# controller.net
KiCad netlist of a schematic drawn in EAGLE
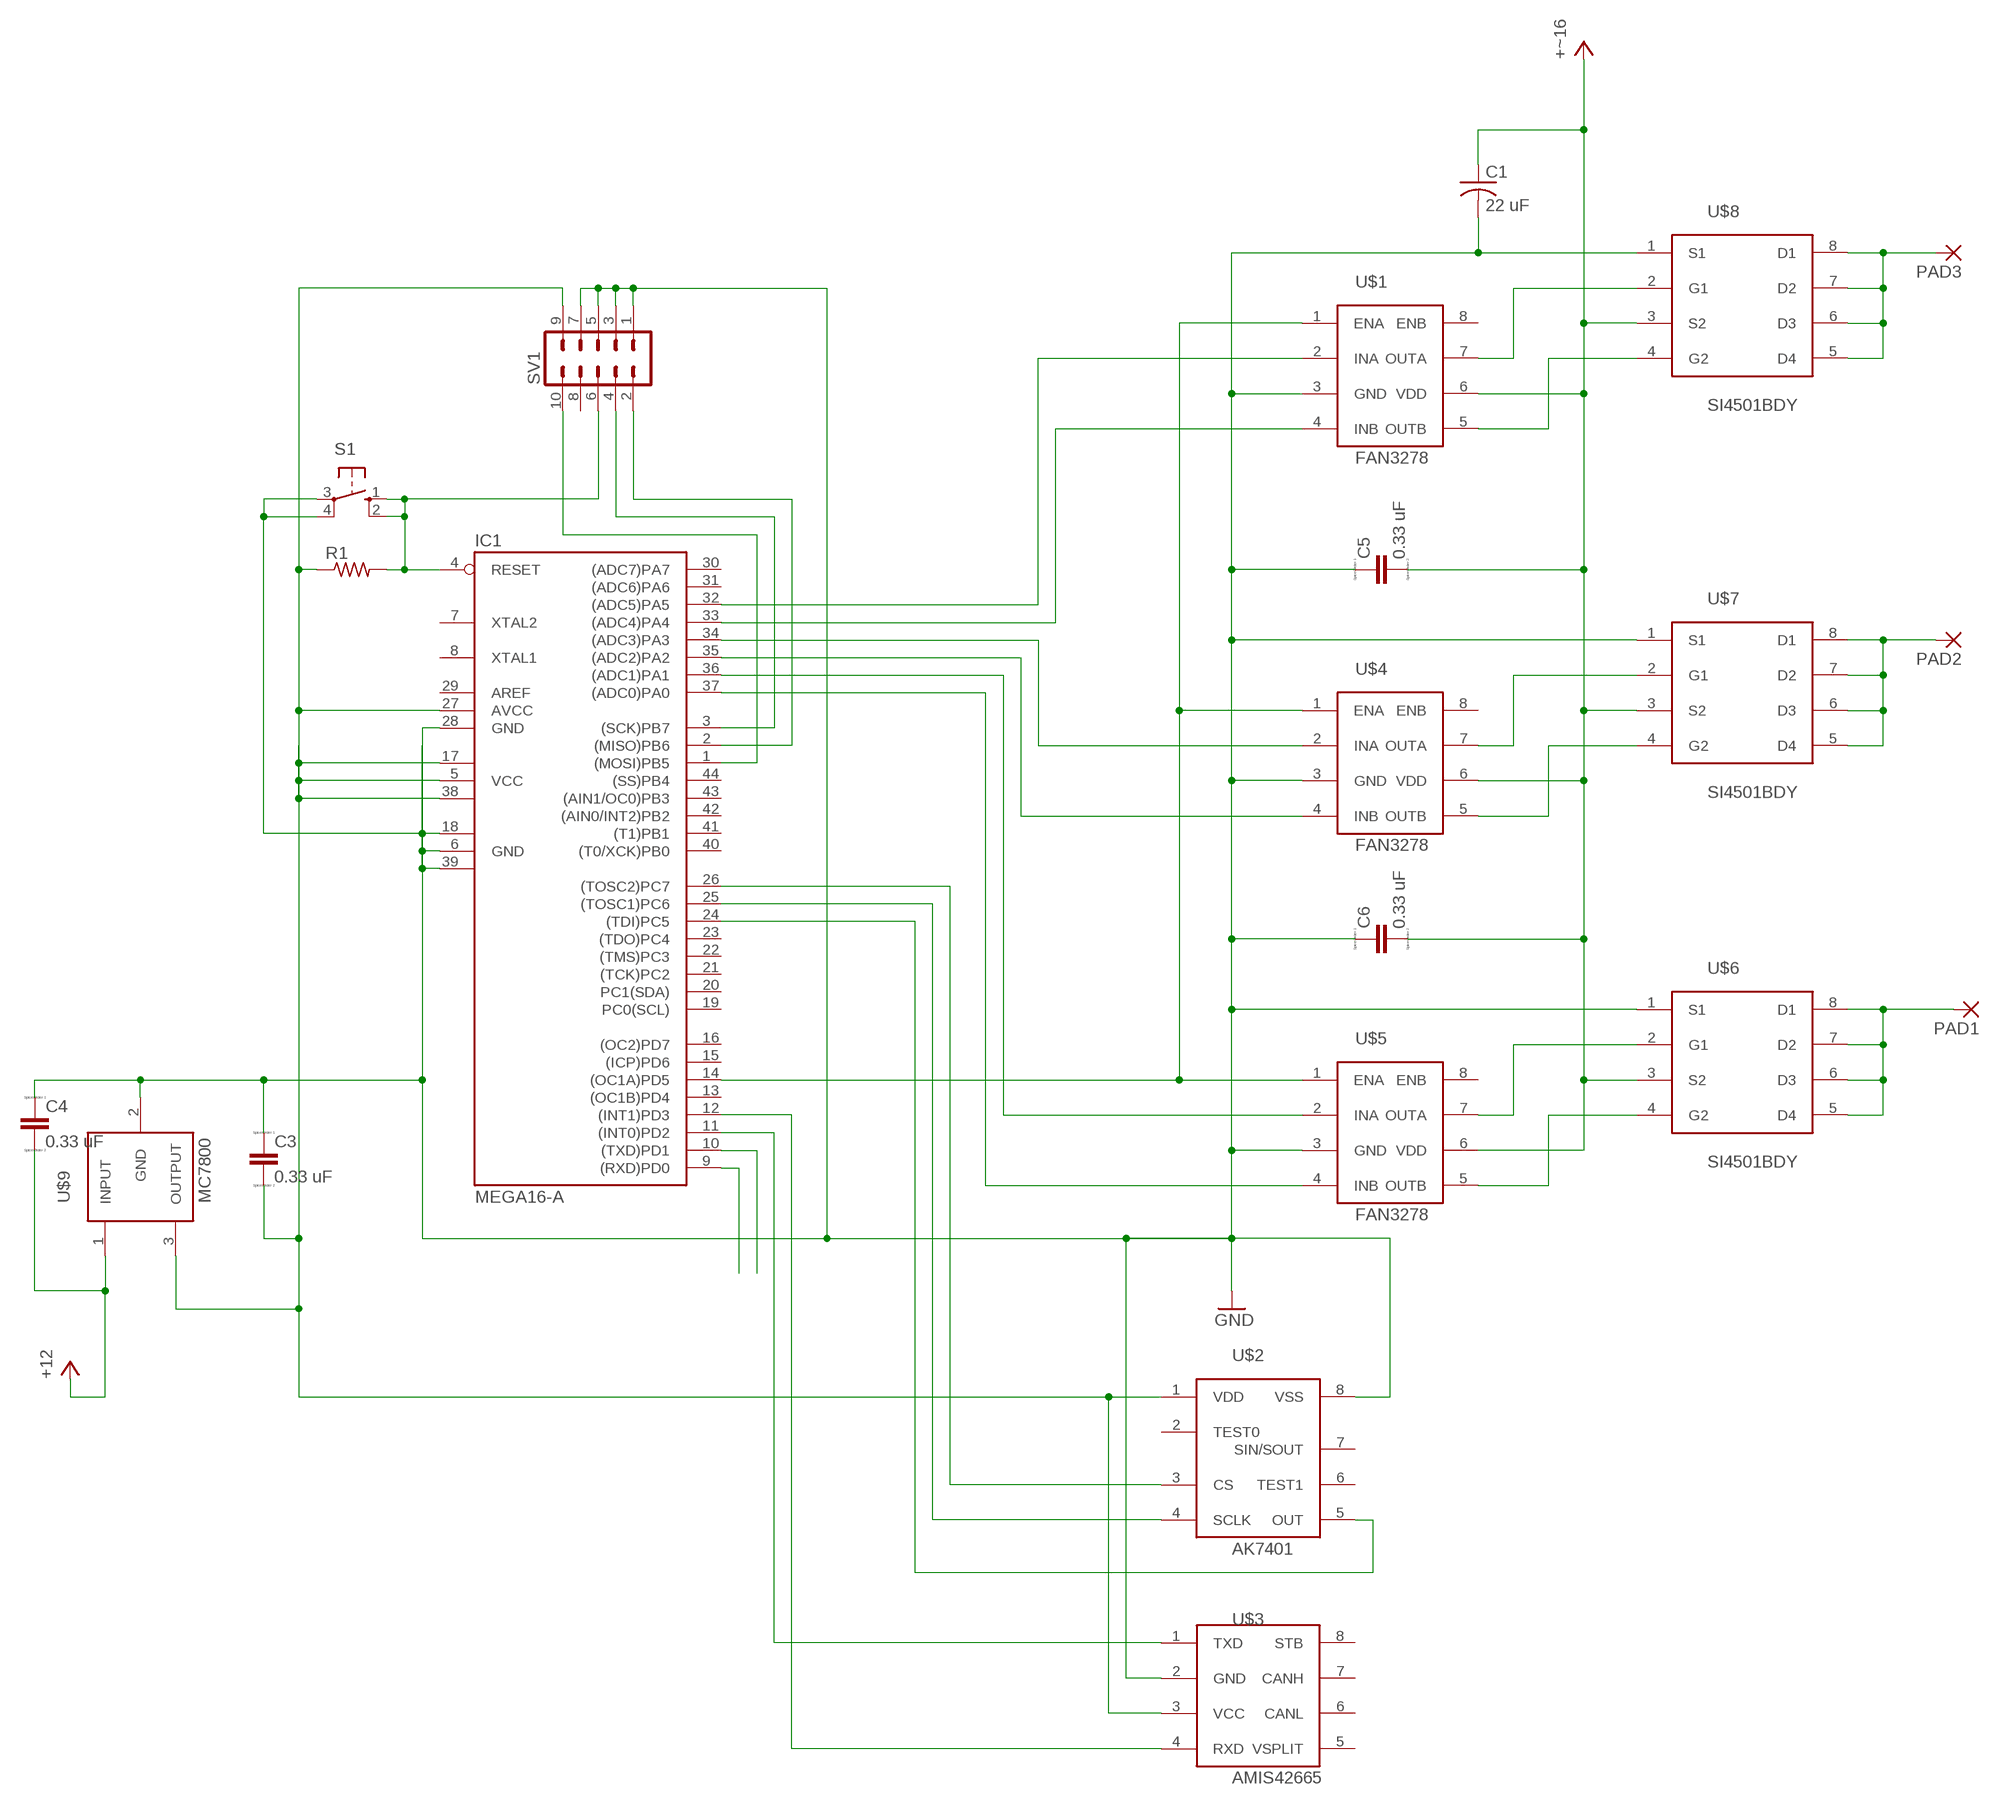
[diagram p0: schematic, sheet 1]

(export (version "E")
  (design (tool "Eeschema 10.0.6"))
  (components
    (comp (ref "C1")
      (value "22 uF")
      (footprint "eagle-import:C1206")
      (libsource (lib "eagle-import") (part "C-USC1206"))
    )
    (comp (ref "C3")
      (value "0.33 uF")
      (footprint "eagle-import:C1206")
      (libsource (lib "eagle-import") (part "CC1206"))
    )
    (comp (ref "C4")
      (value "0.33 uF")
      (footprint "eagle-import:C1206")
      (libsource (lib "eagle-import") (part "CC1206"))
    )
    (comp (ref "C5")
      (value "0.33 uF")
      (footprint "eagle-import:C1206")
      (libsource (lib "eagle-import") (part "CC1206"))
    )
    (comp (ref "C6")
      (value "0.33 uF")
      (footprint "eagle-import:C1206")
      (libsource (lib "eagle-import") (part "CC1206"))
    )
    (comp (ref "IC1")
      (value "MEGA16-A")
      (footprint "eagle-import:TQFP44")
      (fields (field (name "MPN") "ATMEGA16-16AU"))
      (libsource (lib "eagle-import") (part "MEGA16-A"))
    )
    (comp (ref "PAD1")
      (value "2,54/1,0")
      (footprint "eagle-import:2,54_1,0")
      (libsource (lib "eagle-import") (part "2,54/1,0"))
    )
    (comp (ref "PAD2")
      (value "2,54/1,0")
      (footprint "eagle-import:2,54_1,0")
      (libsource (lib "eagle-import") (part "2,54/1,0"))
    )
    (comp (ref "PAD3")
      (value "2,54/1,0")
      (footprint "eagle-import:2,54_1,0")
      (libsource (lib "eagle-import") (part "2,54/1,0"))
    )
    (comp (ref "R1")
      (value "R-US_M1206")
      (footprint "eagle-import:M1206")
      (libsource (lib "eagle-import") (part "R-US_M1206"))
    )
    (comp (ref "S1")
      (value "10-XX")
      (footprint "eagle-import:B3F-10XX")
      (fields (field (name "MPN") "B3F-1000"))
      (libsource (lib "eagle-import") (part "10-XX"))
    )
    (comp (ref "SV1")
      (value "MA05-2")
      (footprint "eagle-import:MA05-2")
      (libsource (lib "eagle-import") (part "MA05-2"))
    )
    (comp (ref "U$1")
      (value "FAN3278")
      (footprint "eagle-import:SOIC-8")
      (libsource (lib "eagle-import") (part "FAN3278"))
    )
    (comp (ref "U$2")
      (value "AK7401")
      (footprint "eagle-import:SOIC-8")
      (libsource (lib "eagle-import") (part "AK7401"))
    )
    (comp (ref "U$3")
      (value "AMIS42665")
      (footprint "eagle-import:SOIC-8")
      (libsource (lib "eagle-import") (part "AMIS42665"))
    )
    (comp (ref "U$4")
      (value "FAN3278")
      (footprint "eagle-import:SOIC-8")
      (libsource (lib "eagle-import") (part "FAN3278"))
    )
    (comp (ref "U$5")
      (value "FAN3278")
      (footprint "eagle-import:SOIC-8")
      (libsource (lib "eagle-import") (part "FAN3278"))
    )
    (comp (ref "U$6")
      (value "SI4501BDY")
      (footprint "eagle-import:SOIC-8")
      (libsource (lib "eagle-import") (part "SI4501BDY"))
    )
    (comp (ref "U$7")
      (value "SI4501BDY")
      (footprint "eagle-import:SOIC-8")
      (libsource (lib "eagle-import") (part "SI4501BDY"))
    )
    (comp (ref "U$8")
      (value "SI4501BDY")
      (footprint "eagle-import:SOIC-8")
      (libsource (lib "eagle-import") (part "SI4501BDY"))
    )
    (comp (ref "U$9")
      (value "MC7800")
      (footprint "eagle-import:TO252")
      (libsource (lib "eagle-import") (part "MC7800"))
    )
  )
  (nets
    (net (code "1") (name "+12") (class "Default")
      (node (ref "C1") (pin "1") (pinfunction "1_1") (pintype "passive"))
      (node (ref "C4") (pin "2") (pinfunction "2_2") (pintype "passive"))
      (node (ref "C5") (pin "2") (pinfunction "2_2") (pintype "passive"))
      (node (ref "C6") (pin "2") (pinfunction "2_2") (pintype "passive"))
      (node (ref "U$1") (pin "6") (pinfunction "VDD_6") (pintype "bidirectional"))
      (node (ref "U$4") (pin "6") (pinfunction "VDD_6") (pintype "bidirectional"))
      (node (ref "U$5") (pin "6") (pinfunction "VDD_6") (pintype "bidirectional"))
      (node (ref "U$6") (pin "3") (pinfunction "S2_3") (pintype "bidirectional"))
      (node (ref "U$7") (pin "3") (pinfunction "S2_3") (pintype "bidirectional"))
      (node (ref "U$8") (pin "3") (pinfunction "S2_3") (pintype "bidirectional"))
      (node (ref "U$9") (pin "1") (pinfunction "INPUT_1") (pintype "bidirectional"))
    )
    (net (code "2") (name "GND") (class "Default")
      (node (ref "C1") (pin "2") (pinfunction "2_2") (pintype "passive"))
      (node (ref "C3") (pin "1") (pinfunction "1_1") (pintype "passive"))
      (node (ref "C4") (pin "1") (pinfunction "1_1") (pintype "passive"))
      (node (ref "C5") (pin "1") (pinfunction "1_1") (pintype "passive"))
      (node (ref "C6") (pin "1") (pinfunction "1_1") (pintype "passive"))
      (node (ref "IC1") (pin "18") (pinfunction "GND1_18") (pintype "power_in"))
      (node (ref "IC1") (pin "28") (pinfunction "GND_28") (pintype "power_in"))
      (node (ref "IC1") (pin "39") (pinfunction "GND2_39") (pintype "power_in"))
      (node (ref "IC1") (pin "6") (pinfunction "GND_6") (pintype "power_in"))
      (node (ref "S1") (pin "3") (pinfunction "P_3") (pintype "passive"))
      (node (ref "S1") (pin "4") (pinfunction "P1_4") (pintype "passive"))
      (node (ref "SV1") (pin "1") (pinfunction "1_1") (pintype "passive"))
      (node (ref "SV1") (pin "3") (pinfunction "3_3") (pintype "passive"))
      (node (ref "SV1") (pin "5") (pinfunction "5_5") (pintype "passive"))
      (node (ref "SV1") (pin "7") (pinfunction "7_7") (pintype "passive"))
      (node (ref "U$1") (pin "3") (pinfunction "GND_3") (pintype "bidirectional"))
      (node (ref "U$2") (pin "8") (pinfunction "VSS_8") (pintype "bidirectional"))
      (node (ref "U$3") (pin "2") (pinfunction "GND_2") (pintype "bidirectional"))
      (node (ref "U$4") (pin "3") (pinfunction "GND_3") (pintype "bidirectional"))
      (node (ref "U$5") (pin "3") (pinfunction "GND_3") (pintype "bidirectional"))
      (node (ref "U$6") (pin "1") (pinfunction "S1_1") (pintype "bidirectional"))
      (node (ref "U$7") (pin "1") (pinfunction "S1_1") (pintype "bidirectional"))
      (node (ref "U$8") (pin "1") (pinfunction "S1_1") (pintype "bidirectional"))
      (node (ref "U$9") (pin "2") (pinfunction "GND_2") (pintype "bidirectional"))
    )
    (net (code "3") (name "Net-(IC1-(ADC0)PA0)") (class "Default")
      (node (ref "IC1") (pin "37") (pinfunction "(ADC0)PA0_37") (pintype "bidirectional"))
      (node (ref "U$5") (pin "4") (pinfunction "INB_4") (pintype "bidirectional"))
    )
    (net (code "4") (name "Net-(IC1-(ADC1)PA1)") (class "Default")
      (node (ref "IC1") (pin "36") (pinfunction "(ADC1)PA1_36") (pintype "bidirectional"))
      (node (ref "U$5") (pin "2") (pinfunction "INA_2") (pintype "bidirectional"))
    )
    (net (code "5") (name "Net-(IC1-(ADC2)PA2)") (class "Default")
      (node (ref "IC1") (pin "35") (pinfunction "(ADC2)PA2_35") (pintype "bidirectional"))
      (node (ref "U$4") (pin "4") (pinfunction "INB_4") (pintype "bidirectional"))
    )
    (net (code "6") (name "Net-(IC1-(ADC3)PA3)") (class "Default")
      (node (ref "IC1") (pin "34") (pinfunction "(ADC3)PA3_34") (pintype "bidirectional"))
      (node (ref "U$4") (pin "2") (pinfunction "INA_2") (pintype "bidirectional"))
    )
    (net (code "7") (name "Net-(IC1-(ADC4)PA4)") (class "Default")
      (node (ref "IC1") (pin "33") (pinfunction "(ADC4)PA4_33") (pintype "bidirectional"))
      (node (ref "U$1") (pin "4") (pinfunction "INB_4") (pintype "bidirectional"))
    )
    (net (code "8") (name "Net-(IC1-(ADC5)PA5)") (class "Default")
      (node (ref "IC1") (pin "32") (pinfunction "(ADC5)PA5_32") (pintype "bidirectional"))
      (node (ref "U$1") (pin "2") (pinfunction "INA_2") (pintype "bidirectional"))
    )
    (net (code "9") (name "Net-(IC1-(INT0)PD2)") (class "Default")
      (node (ref "IC1") (pin "11") (pinfunction "(INT0)PD2_11") (pintype "bidirectional"))
      (node (ref "U$3") (pin "1") (pinfunction "TXD_1") (pintype "bidirectional"))
    )
    (net (code "10") (name "Net-(IC1-(INT1)PD3)") (class "Default")
      (node (ref "IC1") (pin "12") (pinfunction "(INT1)PD3_12") (pintype "bidirectional"))
      (node (ref "U$3") (pin "4") (pinfunction "RXD_4") (pintype "bidirectional"))
    )
    (net (code "11") (name "Net-(IC1-(MISO)PB6)") (class "Default")
      (node (ref "IC1") (pin "2") (pinfunction "(MISO)PB6_2") (pintype "bidirectional"))
      (node (ref "SV1") (pin "2") (pinfunction "2_2") (pintype "passive"))
    )
    (net (code "12") (name "Net-(IC1-(MOSI)PB5)") (class "Default")
      (node (ref "IC1") (pin "1") (pinfunction "(MOSI)PB5_1") (pintype "bidirectional"))
      (node (ref "SV1") (pin "10") (pinfunction "10_10") (pintype "passive"))
    )
    (net (code "13") (name "Net-(IC1-(OC1A)PD5)") (class "Default")
      (node (ref "IC1") (pin "14") (pinfunction "(OC1A)PD5_14") (pintype "bidirectional"))
      (node (ref "U$1") (pin "1") (pinfunction "ENA_1") (pintype "bidirectional"))
      (node (ref "U$4") (pin "1") (pinfunction "ENA_1") (pintype "bidirectional"))
      (node (ref "U$5") (pin "1") (pinfunction "ENA_1") (pintype "bidirectional"))
    )
    (net (code "14") (name "Net-(IC1-(SCK)PB7)") (class "Default")
      (node (ref "IC1") (pin "3") (pinfunction "(SCK)PB7_3") (pintype "bidirectional"))
      (node (ref "SV1") (pin "4") (pinfunction "4_4") (pintype "passive"))
    )
    (net (code "15") (name "Net-(IC1-(TDI)PC5)") (class "Default")
      (node (ref "IC1") (pin "24") (pinfunction "(TDI)PC5_24") (pintype "bidirectional"))
      (node (ref "U$2") (pin "5") (pinfunction "OUT_5") (pintype "bidirectional"))
    )
    (net (code "16") (name "Net-(IC1-(TOSC1)PC6)") (class "Default")
      (node (ref "IC1") (pin "25") (pinfunction "(TOSC1)PC6_25") (pintype "bidirectional"))
      (node (ref "U$2") (pin "4") (pinfunction "SCLK_4") (pintype "bidirectional"))
    )
    (net (code "17") (name "Net-(IC1-(TOSC2)PC7)") (class "Default")
      (node (ref "IC1") (pin "26") (pinfunction "(TOSC2)PC7_26") (pintype "bidirectional"))
      (node (ref "U$2") (pin "3") (pinfunction "CS_3") (pintype "bidirectional"))
    )
    (net (code "18") (name "Net-(IC1-AVCC)") (class "Default")
      (node (ref "C3") (pin "2") (pinfunction "2_2") (pintype "passive"))
      (node (ref "IC1") (pin "17") (pinfunction "VCC1_17") (pintype "power_in"))
      (node (ref "IC1") (pin "27") (pinfunction "AVCC_27") (pintype "power_in"))
      (node (ref "IC1") (pin "38") (pinfunction "VCC2_38") (pintype "power_in"))
      (node (ref "IC1") (pin "5") (pinfunction "VCC_5") (pintype "power_in"))
      (node (ref "R1") (pin "1") (pinfunction "1_1") (pintype "passive"))
      (node (ref "SV1") (pin "9") (pinfunction "9_9") (pintype "passive"))
      (node (ref "U$2") (pin "1") (pinfunction "VDD_1") (pintype "bidirectional"))
      (node (ref "U$3") (pin "3") (pinfunction "VCC_3") (pintype "bidirectional"))
      (node (ref "U$9") (pin "3") (pinfunction "OUTPUT_3") (pintype "bidirectional"))
    )
    (net (code "19") (name "Net-(IC1-RESET)") (class "Default")
      (node (ref "IC1") (pin "4") (pinfunction "RESET_4") (pintype "input"))
      (node (ref "R1") (pin "2") (pinfunction "2_2") (pintype "passive"))
      (node (ref "S1") (pin "1") (pinfunction "S_1") (pintype "passive"))
      (node (ref "S1") (pin "2") (pinfunction "S1_2") (pintype "passive"))
      (node (ref "SV1") (pin "6") (pinfunction "6_6") (pintype "passive"))
    )
    (net (code "20") (name "Net-(PAD1-P)") (class "Default")
      (node (ref "PAD1") (pin "1") (pinfunction "P_1") (pintype "passive"))
      (node (ref "U$6") (pin "5") (pinfunction "D4_5") (pintype "bidirectional"))
      (node (ref "U$6") (pin "6") (pinfunction "D3_6") (pintype "bidirectional"))
      (node (ref "U$6") (pin "7") (pinfunction "D2_7") (pintype "bidirectional"))
      (node (ref "U$6") (pin "8") (pinfunction "D1_8") (pintype "bidirectional"))
    )
    (net (code "21") (name "Net-(PAD2-P)") (class "Default")
      (node (ref "PAD2") (pin "1") (pinfunction "P_1") (pintype "passive"))
      (node (ref "U$7") (pin "5") (pinfunction "D4_5") (pintype "bidirectional"))
      (node (ref "U$7") (pin "6") (pinfunction "D3_6") (pintype "bidirectional"))
      (node (ref "U$7") (pin "7") (pinfunction "D2_7") (pintype "bidirectional"))
      (node (ref "U$7") (pin "8") (pinfunction "D1_8") (pintype "bidirectional"))
    )
    (net (code "22") (name "Net-(PAD3-P)") (class "Default")
      (node (ref "PAD3") (pin "1") (pinfunction "P_1") (pintype "passive"))
      (node (ref "U$8") (pin "5") (pinfunction "D4_5") (pintype "bidirectional"))
      (node (ref "U$8") (pin "6") (pinfunction "D3_6") (pintype "bidirectional"))
      (node (ref "U$8") (pin "7") (pinfunction "D2_7") (pintype "bidirectional"))
      (node (ref "U$8") (pin "8") (pinfunction "D1_8") (pintype "bidirectional"))
    )
    (net (code "23") (name "Net-(U$1-OUTA)") (class "Default")
      (node (ref "U$1") (pin "7") (pinfunction "OUTA_7") (pintype "bidirectional"))
      (node (ref "U$8") (pin "2") (pinfunction "G1_2") (pintype "bidirectional"))
    )
    (net (code "24") (name "Net-(U$1-OUTB)") (class "Default")
      (node (ref "U$1") (pin "5") (pinfunction "OUTB_5") (pintype "bidirectional"))
      (node (ref "U$8") (pin "4") (pinfunction "G2_4") (pintype "bidirectional"))
    )
    (net (code "25") (name "Net-(U$4-OUTA)") (class "Default")
      (node (ref "U$4") (pin "7") (pinfunction "OUTA_7") (pintype "bidirectional"))
      (node (ref "U$7") (pin "2") (pinfunction "G1_2") (pintype "bidirectional"))
    )
    (net (code "26") (name "Net-(U$4-OUTB)") (class "Default")
      (node (ref "U$4") (pin "5") (pinfunction "OUTB_5") (pintype "bidirectional"))
      (node (ref "U$7") (pin "4") (pinfunction "G2_4") (pintype "bidirectional"))
    )
    (net (code "27") (name "Net-(U$5-OUTA)") (class "Default")
      (node (ref "U$5") (pin "7") (pinfunction "OUTA_7") (pintype "bidirectional"))
      (node (ref "U$6") (pin "2") (pinfunction "G1_2") (pintype "bidirectional"))
    )
    (net (code "28") (name "Net-(U$5-OUTB)") (class "Default")
      (node (ref "U$5") (pin "5") (pinfunction "OUTB_5") (pintype "bidirectional"))
      (node (ref "U$6") (pin "4") (pinfunction "G2_4") (pintype "bidirectional"))
    )
    (net (code "29") (name "unconnected-(IC1-(ADC6)PA6-Pad31)") (class "Default")
      (node (ref "IC1") (pin "31") (pinfunction "(ADC6)PA6_31") (pintype "bidirectional"))
    )
    (net (code "30") (name "unconnected-(IC1-(ADC7)PA7-Pad30)") (class "Default")
      (node (ref "IC1") (pin "30") (pinfunction "(ADC7)PA7_30") (pintype "bidirectional"))
    )
    (net (code "31") (name "unconnected-(IC1-(AIN0{slash}INT2)PB2-Pad42)") (class "Default")
      (node (ref "IC1") (pin "42") (pinfunction "(AIN0/INT2)PB2_42") (pintype "bidirectional"))
    )
    (net (code "32") (name "unconnected-(IC1-(AIN1{slash}OC0)PB3-Pad43)") (class "Default")
      (node (ref "IC1") (pin "43") (pinfunction "(AIN1/OC0)PB3_43") (pintype "bidirectional"))
    )
    (net (code "33") (name "unconnected-(IC1-(ICP)PD6-Pad15)") (class "Default")
      (node (ref "IC1") (pin "15") (pinfunction "(ICP)PD6_15") (pintype "bidirectional"))
    )
    (net (code "34") (name "unconnected-(IC1-(OC1B)PD4-Pad13)") (class "Default")
      (node (ref "IC1") (pin "13") (pinfunction "(OC1B)PD4_13") (pintype "bidirectional"))
    )
    (net (code "35") (name "unconnected-(IC1-(OC2)PD7-Pad16)") (class "Default")
      (node (ref "IC1") (pin "16") (pinfunction "(OC2)PD7_16") (pintype "bidirectional"))
    )
    (net (code "36") (name "unconnected-(IC1-(RXD)PD0-Pad9)") (class "Default")
      (node (ref "IC1") (pin "9") (pinfunction "(RXD)PD0_9") (pintype "bidirectional"))
    )
    (net (code "37") (name "unconnected-(IC1-(SS)PB4-Pad44)") (class "Default")
      (node (ref "IC1") (pin "44") (pinfunction "(SS)PB4_44") (pintype "bidirectional"))
    )
    (net (code "38") (name "unconnected-(IC1-(T0{slash}XCK)PB0-Pad40)") (class "Default")
      (node (ref "IC1") (pin "40") (pinfunction "(T0/XCK)PB0_40") (pintype "bidirectional"))
    )
    (net (code "39") (name "unconnected-(IC1-(T1)PB1-Pad41)") (class "Default")
      (node (ref "IC1") (pin "41") (pinfunction "(T1)PB1_41") (pintype "bidirectional"))
    )
    (net (code "40") (name "unconnected-(IC1-(TCK)PC2-Pad21)") (class "Default")
      (node (ref "IC1") (pin "21") (pinfunction "(TCK)PC2_21") (pintype "bidirectional"))
    )
    (net (code "41") (name "unconnected-(IC1-(TDO)PC4-Pad23)") (class "Default")
      (node (ref "IC1") (pin "23") (pinfunction "(TDO)PC4_23") (pintype "bidirectional"))
    )
    (net (code "42") (name "unconnected-(IC1-(TMS)PC3-Pad22)") (class "Default")
      (node (ref "IC1") (pin "22") (pinfunction "(TMS)PC3_22") (pintype "bidirectional"))
    )
    (net (code "43") (name "unconnected-(IC1-(TXD)PD1-Pad10)") (class "Default")
      (node (ref "IC1") (pin "10") (pinfunction "(TXD)PD1_10") (pintype "bidirectional"))
    )
    (net (code "44") (name "unconnected-(IC1-AREF-Pad29)") (class "Default")
      (node (ref "IC1") (pin "29") (pinfunction "AREF_29") (pintype "passive"))
    )
    (net (code "45") (name "unconnected-(IC1-PC0(SCL)-Pad19)") (class "Default")
      (node (ref "IC1") (pin "19") (pinfunction "PC0(SCL)_19") (pintype "bidirectional"))
    )
    (net (code "46") (name "unconnected-(IC1-PC1(SDA)-Pad20)") (class "Default")
      (node (ref "IC1") (pin "20") (pinfunction "PC1(SDA)_20") (pintype "bidirectional"))
    )
    (net (code "47") (name "unconnected-(IC1-XTAL1-Pad8)") (class "Default")
      (node (ref "IC1") (pin "8") (pinfunction "XTAL1_8") (pintype "bidirectional"))
    )
    (net (code "48") (name "unconnected-(IC1-XTAL2-Pad7)") (class "Default")
      (node (ref "IC1") (pin "7") (pinfunction "XTAL2_7") (pintype "bidirectional"))
    )
    (net (code "49") (name "unconnected-(SV1-Pad8)") (class "Default")
      (node (ref "SV1") (pin "8") (pinfunction "8_8") (pintype "passive"))
    )
    (net (code "50") (name "unconnected-(U$1-ENB-Pad8)") (class "Default")
      (node (ref "U$1") (pin "8") (pinfunction "ENB_8") (pintype "bidirectional"))
    )
    (net (code "51") (name "unconnected-(U$2-SIN{slash}SOUT-Pad7)") (class "Default")
      (node (ref "U$2") (pin "7") (pinfunction "SIN/SOUT_7") (pintype "bidirectional"))
    )
    (net (code "52") (name "unconnected-(U$2-TEST0-Pad2)") (class "Default")
      (node (ref "U$2") (pin "2") (pinfunction "TEST0_2") (pintype "bidirectional"))
    )
    (net (code "53") (name "unconnected-(U$2-TEST1-Pad6)") (class "Default")
      (node (ref "U$2") (pin "6") (pinfunction "TEST1_6") (pintype "bidirectional"))
    )
    (net (code "54") (name "unconnected-(U$3-CANH-Pad7)") (class "Default")
      (node (ref "U$3") (pin "7") (pinfunction "CANH_7") (pintype "bidirectional"))
    )
    (net (code "55") (name "unconnected-(U$3-CANL-Pad6)") (class "Default")
      (node (ref "U$3") (pin "6") (pinfunction "CANL_6") (pintype "bidirectional"))
    )
    (net (code "56") (name "unconnected-(U$3-STB-Pad8)") (class "Default")
      (node (ref "U$3") (pin "8") (pinfunction "STB_8") (pintype "bidirectional"))
    )
    (net (code "57") (name "unconnected-(U$3-VSPLIT-Pad5)") (class "Default")
      (node (ref "U$3") (pin "5") (pinfunction "VSPLIT_5") (pintype "bidirectional"))
    )
    (net (code "58") (name "unconnected-(U$4-ENB-Pad8)") (class "Default")
      (node (ref "U$4") (pin "8") (pinfunction "ENB_8") (pintype "bidirectional"))
    )
    (net (code "59") (name "unconnected-(U$5-ENB-Pad8)") (class "Default")
      (node (ref "U$5") (pin "8") (pinfunction "ENB_8") (pintype "bidirectional"))
    )
  )
)
